# 10_ethernet.net
KiCad netlist of a schematic drawn in Altium Designer
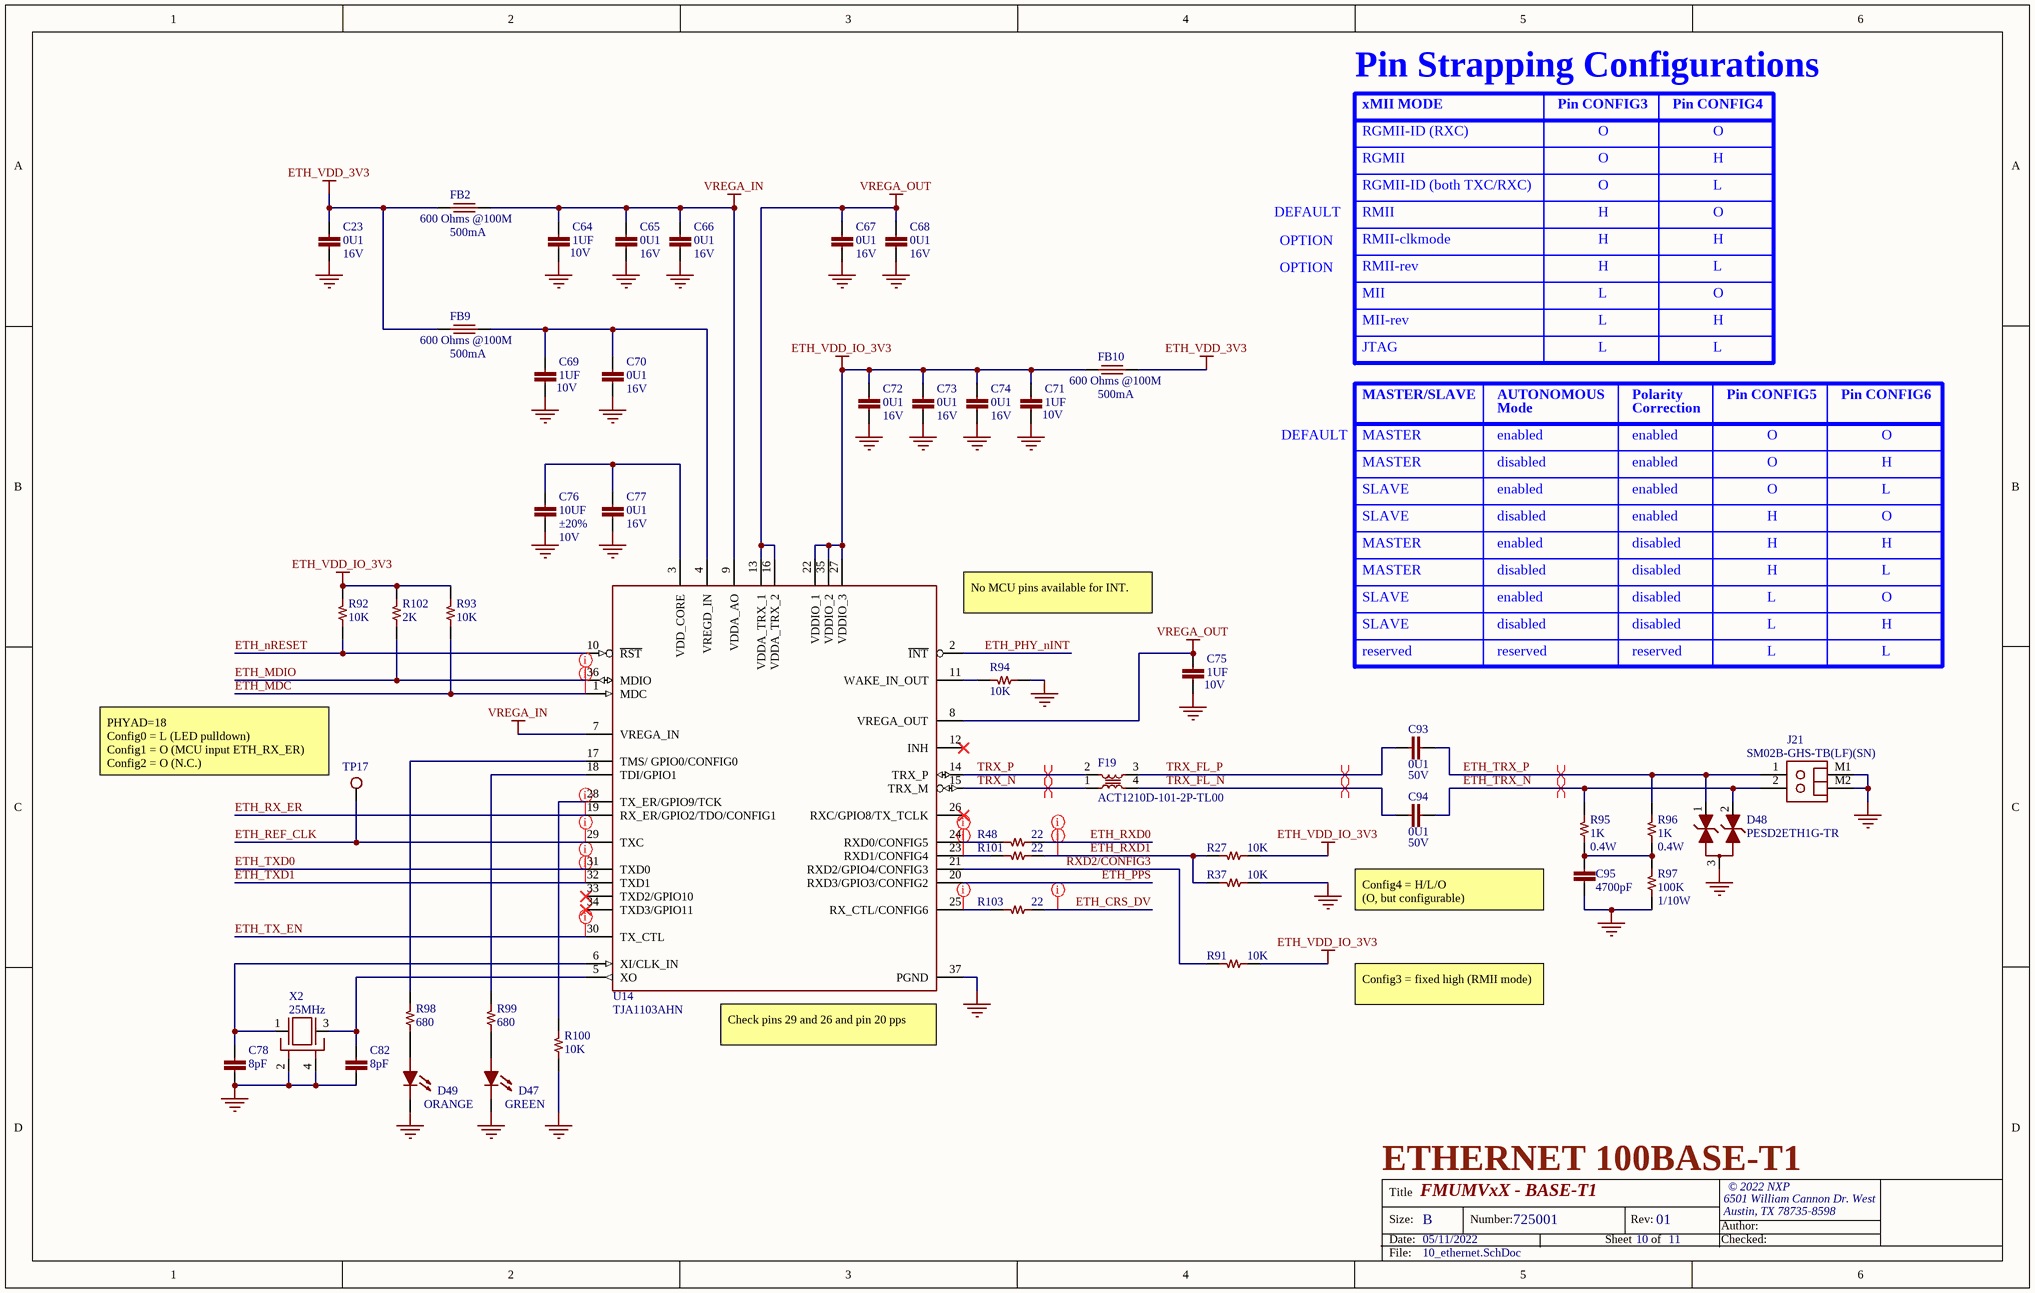
[diagram p0: 10_ethernet.SchDoc]

(export (version "E")
  (design (tool "Eeschema 10.0.6"))
  (components
    (comp (ref "C23")
      (value "0U1")
      (footprint "CAPC100X50X56L25N")
      (description "CAP CER 0.1UF 10% 16V X7R 0402")
      (fields
        (field (name "TOLERANCE") "±10%")
        (field (name "MANUFACTURER") "Murata Electronics")
        (field (name "VOLTAGE - RATED") "16V")
      )
      (libsource (lib "NscDG_Integrated_Library") (part "CAP_0U1_16V_X7R_0402"))
    )
    (comp (ref "C64")
      (value "1UF")
      (footprint "CAPC100X50X56L25N")
      (description "CAP CER 1UF 20% 10V X5R 0402")
      (fields
        (field (name "MANUFACTURER") "Yageo")
        (field (name "MANUFACTURER PART NUMBER") "CC0402MRX5R6BB105")
        (field (name "VOLTAGE - RATED") "10V")
      )
      (libsource (lib "NscDG_Integrated_Library") (part "CAP_1UF_20%_10V_X5R_0402"))
    )
    (comp (ref "C65")
      (value "0U1")
      (footprint "CAPC100X50X56L25N")
      (description "CAP CER 0.1UF 10% 16V X7R 0402")
      (fields
        (field (name "TOLERANCE") "±10%")
        (field (name "MANUFACTURER") "Murata Electronics")
        (field (name "VOLTAGE - RATED") "16V")
      )
      (libsource (lib "NscDG_Integrated_Library") (part "CAP_0U1_16V_X7R_0402"))
    )
    (comp (ref "C66")
      (value "0U1")
      (footprint "CAPC100X50X56L25N")
      (description "CAP CER 0.1UF 10% 16V X7R 0402")
      (fields
        (field (name "TOLERANCE") "±10%")
        (field (name "MANUFACTURER") "Murata Electronics")
        (field (name "VOLTAGE - RATED") "16V")
      )
      (libsource (lib "NscDG_Integrated_Library") (part "CAP_0U1_16V_X7R_0402"))
    )
    (comp (ref "C67")
      (value "0U1")
      (footprint "CAPC100X50X56L25N")
      (description "CAP CER 0.1UF 10% 16V X7R 0402")
      (fields
        (field (name "TOLERANCE") "±10%")
        (field (name "MANUFACTURER") "Murata Electronics")
        (field (name "VOLTAGE - RATED") "16V")
      )
      (libsource (lib "NscDG_Integrated_Library") (part "CAP_0U1_16V_X7R_0402"))
    )
    (comp (ref "C68")
      (value "0U1")
      (footprint "CAPC100X50X56L25N")
      (description "CAP CER 0.1UF 10% 16V X7R 0402")
      (fields
        (field (name "TOLERANCE") "±10%")
        (field (name "MANUFACTURER") "Murata Electronics")
        (field (name "VOLTAGE - RATED") "16V")
      )
      (libsource (lib "NscDG_Integrated_Library") (part "CAP_0U1_16V_X7R_0402"))
    )
    (comp (ref "C69")
      (value "1UF")
      (footprint "CAPC100X50X56L25N")
      (description "CAP CER 1UF 20% 10V X5R 0402")
      (fields
        (field (name "MANUFACTURER") "Yageo")
        (field (name "MANUFACTURER PART NUMBER") "CC0402MRX5R6BB105")
        (field (name "VOLTAGE - RATED") "10V")
      )
      (libsource (lib "NscDG_Integrated_Library") (part "CAP_1UF_20%_10V_X5R_0402"))
    )
    (comp (ref "C70")
      (value "0U1")
      (footprint "CAPC100X50X56L25N")
      (description "CAP CER 0.1UF 10% 16V X7R 0402")
      (fields
        (field (name "TOLERANCE") "±10%")
        (field (name "MANUFACTURER") "Murata Electronics")
        (field (name "VOLTAGE - RATED") "16V")
      )
      (libsource (lib "NscDG_Integrated_Library") (part "CAP_0U1_16V_X7R_0402"))
    )
    (comp (ref "C71")
      (value "1UF")
      (footprint "CAPC100X50X56L25N")
      (description "CAP CER 1UF 20% 10V X5R 0402")
      (fields
        (field (name "MANUFACTURER") "Yageo")
        (field (name "MANUFACTURER PART NUMBER") "CC0402MRX5R6BB105")
        (field (name "VOLTAGE - RATED") "10V")
      )
      (libsource (lib "NscDG_Integrated_Library") (part "CAP_1UF_20%_10V_X5R_0402"))
    )
    (comp (ref "C72")
      (value "0U1")
      (footprint "CAPC100X50X56L25N")
      (description "CAP CER 0.1UF 10% 16V X7R 0402")
      (fields
        (field (name "TOLERANCE") "±10%")
        (field (name "MANUFACTURER") "Murata Electronics")
        (field (name "VOLTAGE - RATED") "16V")
      )
      (libsource (lib "NscDG_Integrated_Library") (part "CAP_0U1_16V_X7R_0402"))
    )
    (comp (ref "C73")
      (value "0U1")
      (footprint "CAPC100X50X56L25N")
      (description "CAP CER 0.1UF 10% 16V X7R 0402")
      (fields
        (field (name "TOLERANCE") "±10%")
        (field (name "MANUFACTURER") "Murata Electronics")
        (field (name "VOLTAGE - RATED") "16V")
      )
      (libsource (lib "NscDG_Integrated_Library") (part "CAP_0U1_16V_X7R_0402"))
    )
    (comp (ref "C74")
      (value "0U1")
      (footprint "CAPC100X50X56L25N")
      (description "CAP CER 0.1UF 10% 16V X7R 0402")
      (fields
        (field (name "TOLERANCE") "±10%")
        (field (name "MANUFACTURER") "Murata Electronics")
        (field (name "VOLTAGE - RATED") "16V")
      )
      (libsource (lib "NscDG_Integrated_Library") (part "CAP_0U1_16V_X7R_0402"))
    )
    (comp (ref "C75")
      (value "1UF")
      (footprint "CAPC100X50X56L25N")
      (description "CAP CER 1UF 20% 10V X5R 0402")
      (fields
        (field (name "MANUFACTURER") "Yageo")
        (field (name "MANUFACTURER PART NUMBER") "CC0402MRX5R6BB105")
        (field (name "VOLTAGE - RATED") "10V")
      )
      (libsource (lib "NscDG_Integrated_Library") (part "CAP_1UF_20%_10V_X5R_0402"))
    )
    (comp (ref "C76")
      (value "10UF")
      (footprint "CAPC100X50X56L25N")
      (description "CAP CER 10UF 20% 10V X5R 0402")
      (fields
        (field (name "MANUFACTURER") "Samsung Electro-Mechanics")
        (field (name "MANUFACTURER PART NUMBER") "CL05A106MP5NUNC")
        (field (name "TOLERANCE") "±20%")
        (field (name "VOLTAGE - RATED") "10V")
      )
      (libsource (lib "NscDG_Integrated_Library") (part "CAP_10UF_20%_10V_X5R_0402"))
    )
    (comp (ref "C77")
      (value "0U1")
      (footprint "CAPC100X50X56L25N")
      (description "CAP CER 0.1UF 10% 16V X7R 0402")
      (fields
        (field (name "TOLERANCE") "±10%")
        (field (name "MANUFACTURER") "Murata Electronics")
        (field (name "VOLTAGE - RATED") "16V")
      )
      (libsource (lib "NscDG_Integrated_Library") (part "CAP_0U1_16V_X7R_0402"))
    )
    (comp (ref "C78")
      (value "8pF")
      (footprint "CAPC100X50X56L25N")
      (description "CAP CER 8PF 50V C0G/NP0 0402")
      (fields
        (field (name "MANUFACTURER") "Yageo")
        (field (name "MANUFACTURER PART NUMBER") "CC0402DRNPO9BN8R0")
      )
      (libsource (lib "NscDG_Integrated_Library") (part "CAP_8PF_50V_NPO_0402"))
    )
    (comp (ref "C82")
      (value "8pF")
      (footprint "CAPC100X50X56L25N")
      (description "CAP CER 8PF 50V C0G/NP0 0402")
      (fields
        (field (name "MANUFACTURER") "Yageo")
        (field (name "MANUFACTURER PART NUMBER") "CC0402DRNPO9BN8R0")
      )
      (libsource (lib "NscDG_Integrated_Library") (part "CAP_8PF_50V_NPO_0402"))
    )
    (comp (ref "C93")
      (value "0U1")
      (footprint "CAPC100X50X56L25N")
      (description "CAP CER 0.1UF 10% 50V X7R 0402")
      (fields
        (field (name "TOLERANCE") "±10%")
        (field (name "MANUFACTURER") "TDK Corporation")
        (field (name "VOLTAGE - RATED") "50V")
      )
      (libsource (lib "NscDG_Integrated_Library") (part "CAP_0U1_50V_X7R_0402"))
    )
    (comp (ref "C94")
      (value "0U1")
      (footprint "CAPC100X50X56L25N")
      (description "CAP CER 0.1UF 10% 50V X7R 0402")
      (fields
        (field (name "TOLERANCE") "±10%")
        (field (name "MANUFACTURER") "TDK Corporation")
        (field (name "VOLTAGE - RATED") "50V")
      )
      (libsource (lib "NscDG_Integrated_Library") (part "CAP_0U1_50V_X7R_0402"))
    )
    (comp (ref "C95")
      (value "4700pF")
      (footprint "CAPC100X50X56L25N")
      (description "CAP CER 4700PF 10% 50V X7R 0402")
      (fields
        (field (name "MANUFACTURER") "Murata Electronics")
        (field (name "MANUFACTURER PART NUMBER") "GRM155R71H472KA01J")
      )
      (libsource (lib "NscDG_Integrated_Library") (part "CAP_4700PF_5%_50V_X7R_0402"))
    )
    (comp (ref "D47")
      (value "LED GREEN CLEAR 0603 SMD")
      (footprint "LEDSC80X160X65L40N_GRN")
      (fields
        (field (name "MANUFACTURER") "Lite-On Inc.")
        (field (name "COLOR") "GREEN")
        (field (name "MANUFACTURER PART NUMBER") "LTST-C191KGKT")
      )
      (libsource (lib "NscDG_Integrated_Library") (part "DIODE_LED_GREEN_0603"))
    )
    (comp (ref "D48")
      (value "DIODE TVS DUAL ETHERNET TO-236AB")
      (footprint "SOT23-3P95_230X110L30X43N_GENERIC")
      (fields
        (field (name "MANUFACTURER") "Nexperia USA Inc.")
        (field (name "MANUFACTURER PART NUMBER") "PESD2ETH1G-TR")
      )
      (libsource (lib "NscDG_Integrated_Library") (part "DIODE_TVS_DUAL_ETHERNET_TO236AB"))
    )
    (comp (ref "D49")
      (value "LED ORANGE CLEAR 0603 SMD")
      (footprint "LEDSC80X160X65L40N_ORA")
      (fields
        (field (name "MANUFACTURER") "Lite-On Inc.")
        (field (name "MANUFACTURER PART NUMBER") "LTST-C191KFKT")
        (field (name "COLOR") "ORANGE")
      )
      (libsource (lib "NscDG_Integrated_Library") (part "DIODE_LED_ORANGE_0603"))
    )
    (comp (ref "F19")
      (value "CMC 100uH 150mA 2LN 5.1KOHMS SMD")
      (footprint "TDK_ACT1210D")
      (fields
        (field (name "MANUFACTURER") "TDK Corporation")
        (field (name "MANUFACTURER PART NUMBER") "ACT1210D-101-2P-TL00")
      )
      (libsource (lib "NscDG_Integrated_Library") (part "FILTER_CMC_100uH_150mA_2LN_SMD"))
    )
    (comp (ref "FB2")
      (value "600 Ohms @100M")
      (footprint "BEADC160X80X95L36N")
      (description "IND FERRITE 600 OHMS @100M 500mA 0603")
      (fields
        (field (name "MANUFACTURER") "Murata Electronics North America")
        (field (name "MANUFACTURER PART NUMBER") "BLM18AG601BH1D")
        (field (name "CURRENT") "500mA")
      )
      (libsource (lib "NscDG_Integrated_Library") (part "IND_FERRITE_600OHM@100M_500mA_0603"))
    )
    (comp (ref "FB9")
      (value "600 Ohms @100M")
      (footprint "BEADC160X80X95L36N")
      (description "IND FERRITE 600 OHMS @100M 500mA 0603")
      (fields
        (field (name "MANUFACTURER") "Murata Electronics North America")
        (field (name "MANUFACTURER PART NUMBER") "BLM18AG601BH1D")
        (field (name "CURRENT") "500mA")
      )
      (libsource (lib "NscDG_Integrated_Library") (part "IND_FERRITE_600OHM@100M_500mA_0603"))
    )
    (comp (ref "FB10")
      (value "600 Ohms @100M")
      (footprint "BEADC160X80X95L36N")
      (description "IND FERRITE 600 OHMS @100M 500mA 0603")
      (fields
        (field (name "MANUFACTURER") "Murata Electronics North America")
        (field (name "MANUFACTURER PART NUMBER") "BLM18AG601BH1D")
        (field (name "CURRENT") "500mA")
      )
      (libsource (lib "NscDG_Integrated_Library") (part "IND_FERRITE_600OHM@100M_500mA_0603"))
    )
    (comp (ref "J21")
      (value "CONN HEADER GH SIDE 2POS 1.25MM SMT")
      (footprint "JST_SM02B-GHS-TBLFSN")
      (fields
        (field (name "MANUFACTURER") "JST Sales America Inc.")
        (field (name "MANUFACTURER PART NUMBER") "SM02B-GHS-TB(LF)(SN)")
      )
      (libsource (lib "NscDG_Integrated_Library") (part "CONN_JST_GH_2PIN_RA_SMT"))
    )
    (comp (ref "R27")
      (value "10K")
      (footprint "RESC100X50X40L25")
      (description "RES SMD 10K OHM 1% 1/16W 0402")
      (fields (field (name "TOLERANCE") "±1%") (field (name "MANUFACTURER") "Vishay Dale"))
      (libsource (lib "NscDG_Integrated_Library") (part "RES_10K_1%_1/16W_0402"))
    )
    (comp (ref "R37")
      (value "10K")
      (footprint "RESC100X50X40L25")
      (description "RES SMD 10K OHM 1% 1/16W 0402")
      (fields (field (name "TOLERANCE") "±1%") (field (name "MANUFACTURER") "Vishay Dale"))
      (libsource (lib "NscDG_Integrated_Library") (part "RES_10K_1%_1/16W_0402"))
    )
    (comp (ref "R48")
      (value "22")
      (footprint "RESC100X50X40L25")
      (description "RES SMD 22 OHM 1% 1/16W 0402")
      (fields (field (name "TOLERANCE") "±1%") (field (name "MANUFACTURER") "Yageo"))
      (libsource (lib "NscDG_Integrated_Library") (part "RES_22R_1%_1/16W_0402"))
    )
    (comp (ref "R91")
      (value "10K")
      (footprint "RESC100X50X40L25")
      (description "RES SMD 10K OHM 1% 1/16W 0402")
      (fields (field (name "TOLERANCE") "±1%") (field (name "MANUFACTURER") "Vishay Dale"))
      (libsource (lib "NscDG_Integrated_Library") (part "RES_10K_1%_1/16W_0402"))
    )
    (comp (ref "R92")
      (value "10K")
      (footprint "RESC100X50X40L25")
      (description "RES SMD 10K OHM 1% 1/16W 0402")
      (fields (field (name "TOLERANCE") "±1%") (field (name "MANUFACTURER") "Vishay Dale"))
      (libsource (lib "NscDG_Integrated_Library") (part "RES_10K_1%_1/16W_0402"))
    )
    (comp (ref "R93")
      (value "10K")
      (footprint "RESC100X50X40L25")
      (description "RES SMD 10K OHM 1% 1/16W 0402")
      (fields (field (name "TOLERANCE") "±1%") (field (name "MANUFACTURER") "Vishay Dale"))
      (libsource (lib "NscDG_Integrated_Library") (part "RES_10K_1%_1/16W_0402"))
    )
    (comp (ref "R94")
      (value "10K")
      (footprint "RESC100X50X40L25")
      (description "RES SMD 10K OHM 1% 1/16W 0402")
      (fields (field (name "TOLERANCE") "±1%") (field (name "MANUFACTURER") "Vishay Dale"))
      (libsource (lib "NscDG_Integrated_Library") (part "RES_10K_1%_1/16W_0402"))
    )
    (comp (ref "R95")
      (value "1K")
      (footprint "RESC200X125X70L40N")
      (description "RES SMD 1K OHM 1% 0.4W 0805")
      (fields
        (field (name "TOLERANCE") "±1%")
        (field (name "MANUFACTURER") "Rohm Semiconductor")
        (field (name "POWER") "0.4W")
      )
      (libsource (lib "NscDG_Integrated_Library") (part "RES_1K_1%_0.4W_0805"))
    )
    (comp (ref "R96")
      (value "1K")
      (footprint "RESC200X125X70L40N")
      (description "RES SMD 1K OHM 1% 0.4W 0805")
      (fields
        (field (name "TOLERANCE") "±1%")
        (field (name "MANUFACTURER") "Rohm Semiconductor")
        (field (name "POWER") "0.4W")
      )
      (libsource (lib "NscDG_Integrated_Library") (part "RES_1K_1%_0.4W_0805"))
    )
    (comp (ref "R97")
      (value "100K")
      (footprint "RESC1608X55L30N")
      (description "RES 100K 1% 1/10W 0603")
      (fields
        (field (name "TOLERANCE") "±1%")
        (field (name "MANUFACTURER") "Yageo")
        (field (name "POWER") "1/10W")
      )
      (libsource (lib "NscDG_Integrated_Library") (part "RES_100K_1%_1/10W_0603"))
    )
    (comp (ref "R98")
      (value "680")
      (footprint "RESC100X50X40L25")
      (description "RES SMD 680 OHM 1% 1/16W 0402")
      (fields (field (name "TOLERANCE") "±1%") (field (name "MANUFACTURER") "Yageo"))
      (libsource (lib "NscDG_Integrated_Library") (part "RES_680_1%_1/16W_0402"))
    )
    (comp (ref "R99")
      (value "680")
      (footprint "RESC100X50X40L25")
      (description "RES SMD 680 OHM 1% 1/16W 0402")
      (fields (field (name "TOLERANCE") "±1%") (field (name "MANUFACTURER") "Yageo"))
      (libsource (lib "NscDG_Integrated_Library") (part "RES_680_1%_1/16W_0402"))
    )
    (comp (ref "R100")
      (value "10K")
      (footprint "RESC100X50X40L25")
      (description "RES SMD 10K OHM 1% 1/16W 0402")
      (fields (field (name "TOLERANCE") "±1%") (field (name "MANUFACTURER") "Vishay Dale"))
      (libsource (lib "NscDG_Integrated_Library") (part "RES_10K_1%_1/16W_0402"))
    )
    (comp (ref "R101")
      (value "22")
      (footprint "RESC100X50X40L25")
      (description "RES SMD 22 OHM 1% 1/16W 0402")
      (fields (field (name "TOLERANCE") "±1%") (field (name "MANUFACTURER") "Yageo"))
      (libsource (lib "NscDG_Integrated_Library") (part "RES_22R_1%_1/16W_0402"))
    )
    (comp (ref "R102")
      (value "2K")
      (footprint "RESC100X50X40L25")
      (description "RES SMD 2K OHM 1% 1/16W 0402")
      (fields (field (name "TOLERANCE") "±1%") (field (name "MANUFACTURER") "Yageo"))
      (libsource (lib "NscDG_Integrated_Library") (part "RES_2K_1%_1/16W_0402"))
    )
    (comp (ref "R103")
      (value "22")
      (footprint "RESC100X50X40L25")
      (description "RES SMD 22 OHM 1% 1/16W 0402")
      (fields (field (name "TOLERANCE") "±1%") (field (name "MANUFACTURER") "Yageo"))
      (libsource (lib "NscDG_Integrated_Library") (part "RES_22R_1%_1/16W_0402"))
    )
    (comp (ref "TP17")
      (value "TESTPOINT PAD SMD")
      (footprint "TEST_PAD_1MM")
      (libsource (lib "NscDG_Integrated_Library") (part "TESTPOINT_PAD_SMD"))
    )
    (comp (ref "U14")
      (value "IC ETHERNET PHY 3.3/2.5/1.1V AEC-Q100 HVQFN36")
      (footprint "QFN37P50_600X600X85L55X24T390N")
      (fields
        (field (name "MANUFACTURER") "NXP SEMICONDUCTORS")
        (field (name "MANUFACTURER PART NUMBER") "TJA1103AHN")
      )
      (libsource (lib "NscDG_Integrated_Library") (part "IC_TJA1103A_ETHERNET_HVQFN36"))
    )
    (comp (ref "X2")
      (value "CRYSTAL 25.0000MHZ 6PF 4-SMD")
      (footprint "OSCCC200X160X70L60X60")
      (fields
        (field (name "MANUFACTURER") "Murata Electronics")
        (field (name "MANUFACTURER PART NUMBER") "XRCGB25M000F3A00R0")
        (field (name "FREQUENCY") "25MHz")
      )
      (libsource (lib "NscDG_Integrated_Library") (part "XTAL_25.0000MHZ_6PF_4-SMD"))
    )
  )
  (nets
    (net (code "1") (name "/ETH_CRS_DV") (class "Default")
      (node (ref "R103") (pin "2") (pinfunction "2_2") (pintype "passive"))
    )
    (net (code "2") (name "/ETH_MDC") (class "Default")
      (node (ref "R93") (pin "2") (pinfunction "2_2") (pintype "passive"))
      (node (ref "U14") (pin "1") (pinfunction "MDC_1") (pintype "input"))
    )
    (net (code "3") (name "/ETH_MDIO") (class "Default")
      (node (ref "R102") (pin "2") (pinfunction "2_2") (pintype "passive"))
      (node (ref "U14") (pin "36") (pinfunction "MDIO_36") (pintype "bidirectional"))
    )
    (net (code "4") (name "/ETH_PHY_nINT") (class "Default")
      (node (ref "U14") (pin "2") (pinfunction "~{INT}_2") (pintype "passive"))
    )
    (net (code "5") (name "/ETH_PPS") (class "Default")
      (node (ref "U14") (pin "20") (pinfunction "RXD3/GPIO3/CONFIG2_20") (pintype "passive"))
    )
    (net (code "6") (name "/ETH_REF_CLK") (class "Default")
      (node (ref "TP17") (pin "1") (pinfunction "1_1") (pintype "passive"))
      (node (ref "U14") (pin "29") (pinfunction "TXC_29") (pintype "passive"))
    )
    (net (code "7") (name "/ETH_RXD0") (class "Default")
      (node (ref "R48") (pin "2") (pinfunction "2_2") (pintype "passive"))
    )
    (net (code "8") (name "/ETH_RXD1") (class "Default")
      (node (ref "R101") (pin "2") (pinfunction "2_2") (pintype "passive"))
      (node (ref "R27") (pin "1") (pinfunction "1_1") (pintype "passive"))
      (node (ref "R37") (pin "1") (pinfunction "1_1") (pintype "passive"))
    )
    (net (code "9") (name "/ETH_RX_ER") (class "Default")
      (node (ref "U14") (pin "19") (pinfunction "RX_ER/GPIO2/TDO/CONFIG1_19") (pintype "passive"))
    )
    (net (code "10") (name "/ETH_TRX_N") (class "Default")
      (node (ref "C94") (pin "2") (pinfunction "2_2") (pintype "passive"))
      (node (ref "D48") (pin "2") (pinfunction "2_2") (pintype "passive"))
      (node (ref "J21") (pin "2") (pinfunction "2_2") (pintype "passive"))
      (node (ref "R95") (pin "1") (pinfunction "1_1") (pintype "passive"))
    )
    (net (code "11") (name "/ETH_TRX_P") (class "Default")
      (node (ref "C93") (pin "2") (pinfunction "2_2") (pintype "passive"))
      (node (ref "D48") (pin "1") (pinfunction "1_1") (pintype "passive"))
      (node (ref "J21") (pin "1") (pinfunction "1_1") (pintype "passive"))
      (node (ref "R96") (pin "1") (pinfunction "1_1") (pintype "passive"))
    )
    (net (code "12") (name "/ETH_TXD0") (class "Default")
      (node (ref "U14") (pin "31") (pinfunction "TXD0_31") (pintype "passive"))
    )
    (net (code "13") (name "/ETH_TXD1") (class "Default")
      (node (ref "U14") (pin "32") (pinfunction "TXD1_32") (pintype "passive"))
    )
    (net (code "14") (name "/ETH_TX_EN") (class "Default")
      (node (ref "U14") (pin "30") (pinfunction "TX_CTL_30") (pintype "passive"))
    )
    (net (code "15") (name "/ETH_nRESET") (class "Default")
      (node (ref "R92") (pin "2") (pinfunction "2_2") (pintype "passive"))
      (node (ref "U14") (pin "10") (pinfunction "~{RST}_10") (pintype "input"))
    )
    (net (code "16") (name "/RXD2{slash}CONFIG3") (class "Default")
      (node (ref "R91") (pin "1") (pinfunction "1_1") (pintype "passive"))
      (node (ref "U14") (pin "21") (pinfunction "RXD2/GPIO4/CONFIG3_21") (pintype "passive"))
    )
    (net (code "17") (name "/TRX_FL_N") (class "Default")
      (node (ref "C94") (pin "1") (pinfunction "1_1") (pintype "passive"))
      (node (ref "F19") (pin "4") (pinfunction "4_4") (pintype "passive"))
    )
    (net (code "18") (name "/TRX_FL_P") (class "Default")
      (node (ref "C93") (pin "1") (pinfunction "1_1") (pintype "passive"))
      (node (ref "F19") (pin "3") (pinfunction "3_3") (pintype "passive"))
    )
    (net (code "19") (name "/TRX_N") (class "Default")
      (node (ref "F19") (pin "1") (pinfunction "1_1") (pintype "passive"))
      (node (ref "U14") (pin "15") (pinfunction "TRX_M_15") (pintype "bidirectional"))
    )
    (net (code "20") (name "/TRX_P") (class "Default")
      (node (ref "F19") (pin "2") (pinfunction "2_2") (pintype "passive"))
      (node (ref "U14") (pin "14") (pinfunction "TRX_P_14") (pintype "bidirectional"))
    )
    (net (code "21") (name "ETH_VDD_3V3") (class "Default")
      (node (ref "C23") (pin "1") (pinfunction "1_1") (pintype "passive"))
      (node (ref "FB10") (pin "2") (pinfunction "2_2") (pintype "passive"))
      (node (ref "FB2") (pin "1") (pinfunction "1_1") (pintype "passive"))
      (node (ref "FB9") (pin "1") (pinfunction "1_1") (pintype "passive"))
    )
    (net (code "22") (name "ETH_VDD_IO_3V3") (class "Default")
      (node (ref "C71") (pin "1") (pinfunction "1_1") (pintype "passive"))
      (node (ref "C72") (pin "1") (pinfunction "1_1") (pintype "passive"))
      (node (ref "C73") (pin "1") (pinfunction "1_1") (pintype "passive"))
      (node (ref "C74") (pin "1") (pinfunction "1_1") (pintype "passive"))
      (node (ref "FB10") (pin "1") (pinfunction "1_1") (pintype "passive"))
      (node (ref "R102") (pin "1") (pinfunction "1_1") (pintype "passive"))
      (node (ref "R27") (pin "2") (pinfunction "2_2") (pintype "passive"))
      (node (ref "R91") (pin "2") (pinfunction "2_2") (pintype "passive"))
      (node (ref "R92") (pin "1") (pinfunction "1_1") (pintype "passive"))
      (node (ref "R93") (pin "1") (pinfunction "1_1") (pintype "passive"))
      (node (ref "U14") (pin "22") (pinfunction "VDDIO_1_22") (pintype "power_in"))
      (node (ref "U14") (pin "27") (pinfunction "VDDIO_3_27") (pintype "passive"))
      (node (ref "U14") (pin "35") (pinfunction "VDDIO_2_35") (pintype "power_in"))
    )
    (net (code "23") (name "GND") (class "Default")
      (node (ref "C23") (pin "2") (pinfunction "2_2") (pintype "passive"))
      (node (ref "C64") (pin "2") (pinfunction "2_2") (pintype "passive"))
      (node (ref "C65") (pin "2") (pinfunction "2_2") (pintype "passive"))
      (node (ref "C66") (pin "2") (pinfunction "2_2") (pintype "passive"))
      (node (ref "C67") (pin "2") (pinfunction "2_2") (pintype "passive"))
      (node (ref "C68") (pin "2") (pinfunction "2_2") (pintype "passive"))
      (node (ref "C69") (pin "2") (pinfunction "2_2") (pintype "passive"))
      (node (ref "C70") (pin "2") (pinfunction "2_2") (pintype "passive"))
      (node (ref "C71") (pin "2") (pinfunction "2_2") (pintype "passive"))
      (node (ref "C72") (pin "2") (pinfunction "2_2") (pintype "passive"))
      (node (ref "C73") (pin "2") (pinfunction "2_2") (pintype "passive"))
      (node (ref "C74") (pin "2") (pinfunction "2_2") (pintype "passive"))
      (node (ref "C75") (pin "2") (pinfunction "2_2") (pintype "passive"))
      (node (ref "C76") (pin "2") (pinfunction "2_2") (pintype "passive"))
      (node (ref "C77") (pin "2") (pinfunction "2_2") (pintype "passive"))
      (node (ref "C78") (pin "2") (pinfunction "2_2") (pintype "passive"))
      (node (ref "C82") (pin "2") (pinfunction "2_2") (pintype "passive"))
      (node (ref "C95") (pin "2") (pinfunction "2_2") (pintype "passive"))
      (node (ref "D47") (pin "C") (pinfunction "C_C") (pintype "passive"))
      (node (ref "D48") (pin "3") (pinfunction "3_3") (pintype "passive"))
      (node (ref "D49") (pin "C") (pinfunction "C_C") (pintype "passive"))
      (node (ref "J21") (pin "M1") (pinfunction "M1_M1") (pintype "passive"))
      (node (ref "J21") (pin "M2") (pinfunction "M2_M2") (pintype "passive"))
      (node (ref "R100") (pin "2") (pinfunction "2_2") (pintype "passive"))
      (node (ref "R37") (pin "2") (pinfunction "2_2") (pintype "passive"))
      (node (ref "R94") (pin "2") (pinfunction "2_2") (pintype "passive"))
      (node (ref "R97") (pin "2") (pinfunction "2_2") (pintype "passive"))
      (node (ref "U14") (pin "37") (pinfunction "PGND_37") (pintype "passive"))
      (node (ref "X2") (pin "2") (pinfunction "2_2") (pintype "passive"))
      (node (ref "X2") (pin "4") (pinfunction "4_4") (pintype "passive"))
    )
    (net (code "24") (name "Net-(C95-Pad1)") (class "Default")
      (node (ref "C95") (pin "1") (pinfunction "1_1") (pintype "passive"))
      (node (ref "R95") (pin "2") (pinfunction "2_2") (pintype "passive"))
      (node (ref "R96") (pin "2") (pinfunction "2_2") (pintype "passive"))
      (node (ref "R97") (pin "1") (pinfunction "1_1") (pintype "passive"))
    )
    (net (code "25") (name "Net-(D47-PadA)") (class "Default")
      (node (ref "D47") (pin "A") (pinfunction "A_A") (pintype "passive"))
      (node (ref "R99") (pin "2") (pinfunction "2_2") (pintype "passive"))
    )
    (net (code "26") (name "Net-(D49-PadA)") (class "Default")
      (node (ref "D49") (pin "A") (pinfunction "A_A") (pintype "passive"))
      (node (ref "R98") (pin "2") (pinfunction "2_2") (pintype "passive"))
    )
    (net (code "27") (name "Net-(U14-RXD0{slash}CONFIG5)") (class "Default")
      (node (ref "R48") (pin "1") (pinfunction "1_1") (pintype "passive"))
      (node (ref "U14") (pin "24") (pinfunction "RXD0/CONFIG5_24") (pintype "passive"))
    )
    (net (code "28") (name "Net-(U14-RXD1{slash}CONFIG4)") (class "Default")
      (node (ref "R101") (pin "1") (pinfunction "1_1") (pintype "passive"))
      (node (ref "U14") (pin "23") (pinfunction "RXD1/CONFIG4_23") (pintype "passive"))
    )
    (net (code "29") (name "Net-(U14-RX_CTL{slash}CONFIG6)") (class "Default")
      (node (ref "R103") (pin "1") (pinfunction "1_1") (pintype "passive"))
      (node (ref "U14") (pin "25") (pinfunction "RX_CTL/CONFIG6_25") (pintype "passive"))
    )
    (net (code "30") (name "Net-(U14-TDI{slash}GPIO1)") (class "Default")
      (node (ref "R99") (pin "1") (pinfunction "1_1") (pintype "passive"))
      (node (ref "U14") (pin "18") (pinfunction "TDI/GPIO1_18") (pintype "passive"))
    )
    (net (code "31") (name "Net-(U14-TMS{slash}_GPIO0{slash}CONFIG0)") (class "Default")
      (node (ref "R98") (pin "1") (pinfunction "1_1") (pintype "passive"))
      (node (ref "U14") (pin "17") (pinfunction "TMS/_GPIO0/CONFIG0_17") (pintype "passive"))
    )
    (net (code "32") (name "Net-(U14-TX_ER{slash}GPIO9{slash}TCK)") (class "Default")
      (node (ref "R100") (pin "1") (pinfunction "1_1") (pintype "passive"))
      (node (ref "U14") (pin "28") (pinfunction "TX_ER/GPIO9/TCK_28") (pintype "passive"))
    )
    (net (code "33") (name "Net-(U14-VDD_CORE)") (class "Default")
      (node (ref "C76") (pin "1") (pinfunction "1_1") (pintype "passive"))
      (node (ref "C77") (pin "1") (pinfunction "1_1") (pintype "passive"))
      (node (ref "U14") (pin "3") (pinfunction "VDD_CORE_3") (pintype "power_in"))
    )
    (net (code "34") (name "Net-(U14-VREGD_IN)") (class "Default")
      (node (ref "C69") (pin "1") (pinfunction "1_1") (pintype "passive"))
      (node (ref "C70") (pin "1") (pinfunction "1_1") (pintype "passive"))
      (node (ref "FB9") (pin "2") (pinfunction "2_2") (pintype "passive"))
      (node (ref "U14") (pin "4") (pinfunction "VREGD_IN_4") (pintype "power_in"))
    )
    (net (code "35") (name "Net-(U14-WAKE_IN_OUT)") (class "Default")
      (node (ref "R94") (pin "1") (pinfunction "1_1") (pintype "passive"))
      (node (ref "U14") (pin "11") (pinfunction "WAKE_IN_OUT_11") (pintype "passive"))
    )
    (net (code "36") (name "Net-(U14-XI{slash}CLK_IN)") (class "Default")
      (node (ref "C78") (pin "1") (pinfunction "1_1") (pintype "passive"))
      (node (ref "U14") (pin "6") (pinfunction "XI/CLK_IN_6") (pintype "input"))
      (node (ref "X2") (pin "1") (pinfunction "1_1") (pintype "passive"))
    )
    (net (code "37") (name "Net-(U14-XO)") (class "Default")
      (node (ref "C82") (pin "1") (pinfunction "1_1") (pintype "passive"))
      (node (ref "U14") (pin "5") (pinfunction "XO_5") (pintype "output"))
      (node (ref "X2") (pin "3") (pinfunction "3_3") (pintype "passive"))
    )
    (net (code "38") (name "VREGA_IN") (class "Default")
      (node (ref "C64") (pin "1") (pinfunction "1_1") (pintype "passive"))
      (node (ref "C65") (pin "1") (pinfunction "1_1") (pintype "passive"))
      (node (ref "C66") (pin "1") (pinfunction "1_1") (pintype "passive"))
      (node (ref "FB2") (pin "2") (pinfunction "2_2") (pintype "passive"))
      (node (ref "U14") (pin "7") (pinfunction "VREGA_IN_7") (pintype "power_in"))
      (node (ref "U14") (pin "9") (pinfunction "VDDA_AO_9") (pintype "power_in"))
    )
    (net (code "39") (name "VREGA_OUT") (class "Default")
      (node (ref "C67") (pin "1") (pinfunction "1_1") (pintype "passive"))
      (node (ref "C68") (pin "1") (pinfunction "1_1") (pintype "passive"))
      (node (ref "C75") (pin "1") (pinfunction "1_1") (pintype "passive"))
      (node (ref "U14") (pin "13") (pinfunction "VDDA_TRX_1_13") (pintype "power_in"))
      (node (ref "U14") (pin "16") (pinfunction "VDDA_TRX_2_16") (pintype "power_in"))
      (node (ref "U14") (pin "8") (pinfunction "VREGA_OUT_8") (pintype "power_in"))
    )
    (net (code "40") (name "unconnected-(U14-INH-Pad12)") (class "Default")
      (node (ref "U14") (pin "12") (pinfunction "INH_12") (pintype "passive+no_connect"))
    )
    (net (code "41") (name "unconnected-(U14-RXC{slash}GPIO8{slash}TX_TCLK-Pad26)") (class "Default")
      (node (ref "U14") (pin "26") (pinfunction "RXC/GPIO8/TX_TCLK_26") (pintype "passive+no_connect"))
    )
    (net (code "42") (name "unconnected-(U14-TXD2{slash}GPIO10-Pad33)") (class "Default")
      (node (ref "U14") (pin "33") (pinfunction "TXD2/GPIO10_33") (pintype "passive+no_connect"))
    )
    (net (code "43") (name "unconnected-(U14-TXD3{slash}GPIO11-Pad34)") (class "Default")
      (node (ref "U14") (pin "34") (pinfunction "TXD3/GPIO11_34") (pintype "passive+no_connect"))
    )
  )
)
